# Main.net
KiCad netlist of a schematic drawn in Altium Designer
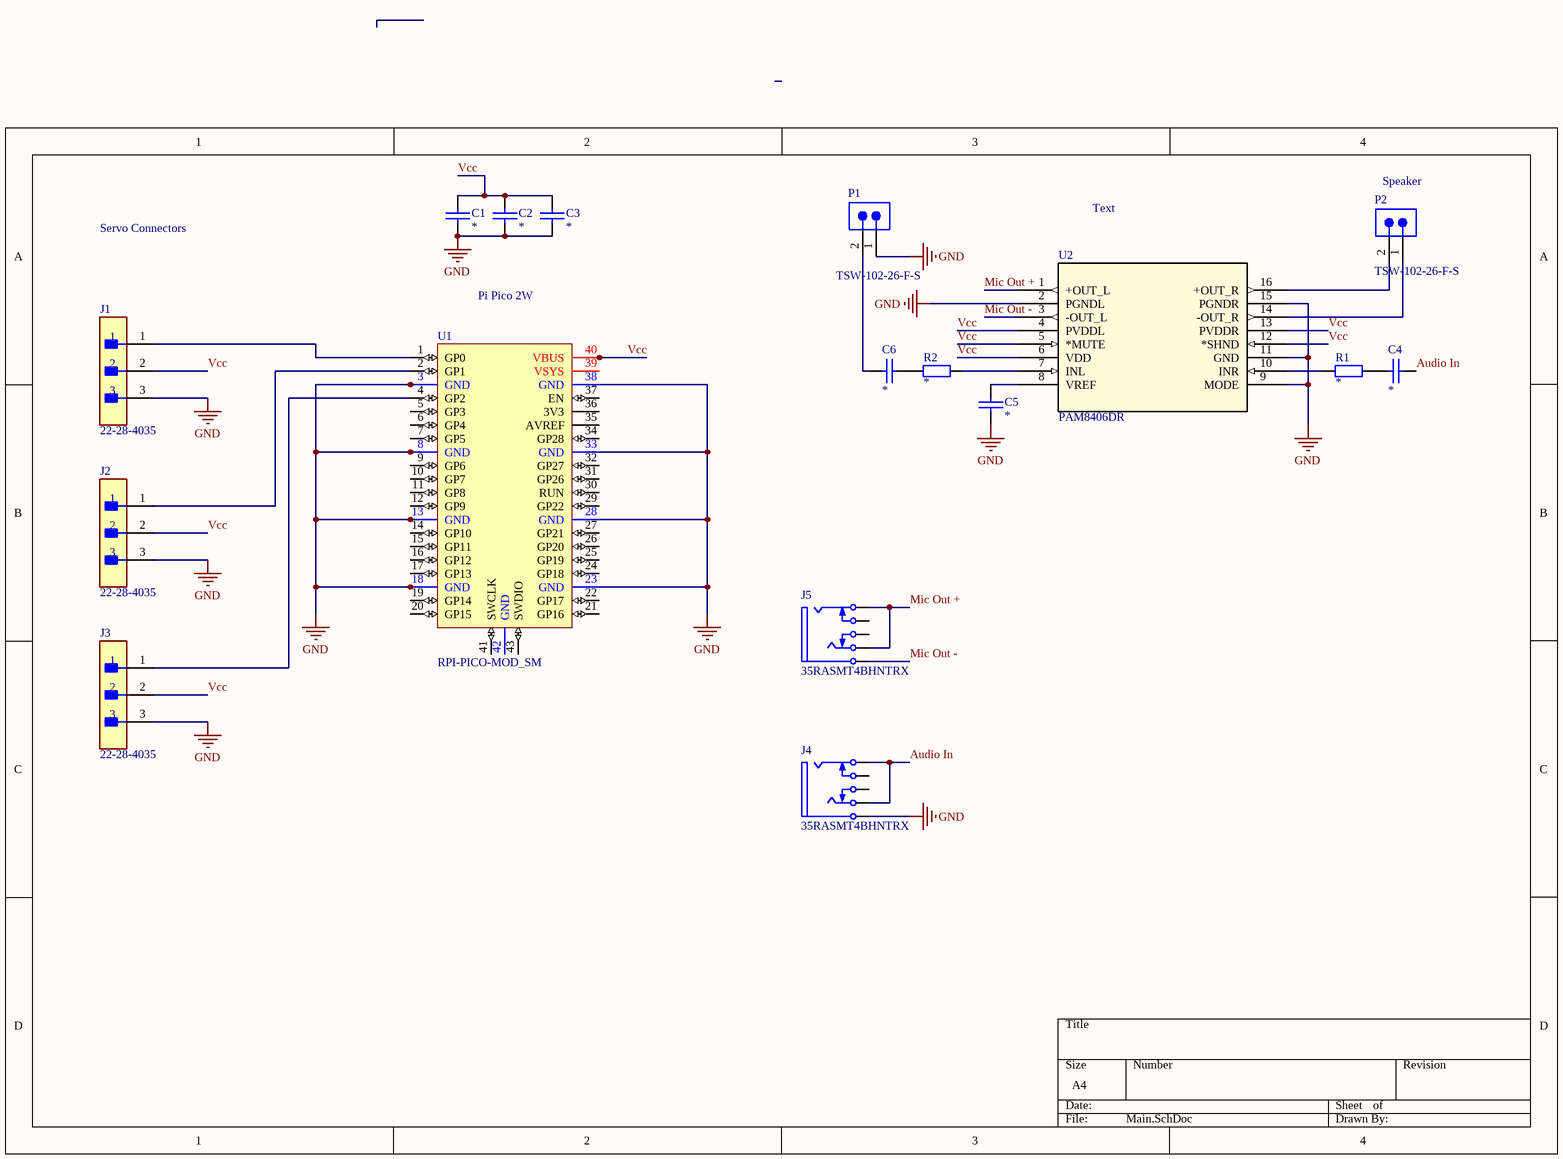
[diagram p0: Main.SchDoc]

(export (version "E")
  (design (tool "Eeschema 10.0.6"))
  (components
    (comp (ref "C1")
      (value "*")
      (footprint "0805 CAP")
      (description "SMT ceramic capacitor 0805 size")
      (libsource (lib "EE209_SchLib") (part "CerCap_SMT_0805"))
    )
    (comp (ref "C2")
      (value "*")
      (footprint "0805 CAP")
      (description "SMT ceramic capacitor 0805 size")
      (libsource (lib "EE209_SchLib") (part "CerCap_SMT_0805"))
    )
    (comp (ref "C3")
      (value "*")
      (footprint "0805 CAP")
      (description "SMT ceramic capacitor 0805 size")
      (libsource (lib "EE209_SchLib") (part "CerCap_SMT_0805"))
    )
    (comp (ref "C4")
      (value "*")
      (footprint "0805 CAP")
      (description "SMT ceramic capacitor 0805 size")
      (libsource (lib "EE209_SchLib") (part "CerCap_SMT_0805"))
    )
    (comp (ref "C5")
      (value "*")
      (footprint "0805 CAP")
      (description "SMT ceramic capacitor 0805 size")
      (libsource (lib "EE209_SchLib") (part "CerCap_SMT_0805"))
    )
    (comp (ref "C6")
      (value "*")
      (footprint "0805 CAP")
      (description "SMT ceramic capacitor 0805 size")
      (libsource (lib "EE209_SchLib") (part "CerCap_SMT_0805"))
    )
    (comp (ref "J1")
      (value "22-28-4035")
      (footprint "FP-22-28-4035-MFG")
      (libsource (lib "Altium Content Vault") (part "0d3f023dd272f625e17a2be33dea85f"))
    )
    (comp (ref "J2")
      (value "22-28-4035")
      (footprint "FP-22-28-4035-MFG")
      (libsource (lib "Altium Content Vault") (part "0d3f023dd272f625e17a2be33dea85f"))
    )
    (comp (ref "J3")
      (value "22-28-4035")
      (footprint "FP-22-28-4035-MFG")
      (libsource (lib "Altium Content Vault") (part "0d3f023dd272f625e17a2be33dea85f"))
    )
    (comp (ref "J4")
      (value "35RASMT4BHNTRX")
      (footprint "SWIT-35RASMT4BHNTRX_V")
      (description "Female 3.5 mm Phone Jack, 5 Position, Height 5 mm, RoHS, Tape and Reel")
      (libsource (lib "Altium Content Vault") (part "JACK-3CD5-RN"))
    )
    (comp (ref "J5")
      (value "35RASMT4BHNTRX")
      (footprint "SWIT-35RASMT4BHNTRX_V")
      (description "Female 3.5 mm Phone Jack, 5 Position, Height 5 mm, RoHS, Tape and Reel")
      (libsource (lib "Altium Content Vault") (part "JACK-3CD5-RN"))
    )
    (comp (ref "P1")
      (value "TSW-102-26-F-S")
      (footprint "SMTC-TSW-102-26-XX-S")
      (description "0.025\" SQ Post Header, Through-hole, Vertical, -55 to 125 degC, 2.54 mm Pitch, 2-Pin, Male, RoHS")
      (fields (field (name "MANUFACTURER") "Samtec"))
      (libsource (lib "Altium Content Vault") (part "SMTC-TSW-102-X-X-S-X"))
    )
    (comp (ref "P2")
      (value "TSW-102-26-F-S")
      (footprint "SMTC-TSW-102-26-XX-S")
      (description "0.025\" SQ Post Header, Through-hole, Vertical, -55 to 125 degC, 2.54 mm Pitch, 2-Pin, Male, RoHS")
      (fields (field (name "MANUFACTURER") "Samtec"))
      (libsource (lib "Altium Content Vault") (part "SMTC-TSW-102-X-X-S-X"))
    )
    (comp (ref "R1")
      (value "*")
      (footprint "0805 RES")
      (description "0805 resistor")
      (fields (field (name "PUBLISHER") "Altium Limited"))
      (libsource (lib "") (part "Res_SMT_0805_1"))
    )
    (comp (ref "R2")
      (value "*")
      (footprint "0805 RES")
      (description "0805 resistor")
      (fields (field (name "PUBLISHER") "Altium Limited"))
      (libsource (lib "EE209_SchLib") (part "Res_SMT_0805"))
    )
    (comp (ref "U1")
      (value "RPI-PICO-MOD_SM")
      (footprint "RPI-PICO-MOD")
      (description "RASPBERRY PI PICO RP2040 BOARD NO TEST PADS")
      (fields
        (field (name "MANUFACTURER") "Raspberry Pi Foundation")
        (field (name "MANUFACTURER PART NO") "SC0915")
      )
      (libsource (lib "RPi_Pico") (part "RPI-PICO-MOD_SM"))
    )
    (comp (ref "U2")
      (value "PAM8406DR")
      (footprint "SO-16_PAM8406_DIO")
      (description "Description")
      (fields (field (name "COPYRIGHT") "Copyright (C) 2025 Ultra Librarian. All rights reserved."))
      (libsource (lib "PAM8406DR") (part "PAM8406DR"))
    )
  )
  (nets
    (net (code "1") (name "/Audio In") (class "Default")
      (node (ref "C4") (pin "2") (pinfunction "2_2") (pintype "passive"))
      (node (ref "J4") (pin "2") (pinfunction "2_2") (pintype "passive"))
      (node (ref "J4") (pin "3") (pinfunction "3_3") (pintype "passive"))
    )
    (net (code "2") (name "/Mic Out +") (class "Default")
      (node (ref "J5") (pin "2") (pinfunction "2_2") (pintype "passive"))
      (node (ref "J5") (pin "3") (pinfunction "3_3") (pintype "passive"))
      (node (ref "U2") (pin "1") (pinfunction "+OUT_L_1") (pintype "output"))
    )
    (net (code "3") (name "/Mic Out -") (class "Default")
      (node (ref "J5") (pin "1") (pinfunction "1_1") (pintype "passive"))
      (node (ref "U2") (pin "3") (pinfunction "-OUT_L_3") (pintype "output"))
    )
    (net (code "4") (name "/Vcc") (class "Default")
      (node (ref "C1") (pin "1") (pinfunction "1_1") (pintype "passive"))
      (node (ref "C2") (pin "1") (pinfunction "1_1") (pintype "passive"))
      (node (ref "C3") (pin "1") (pinfunction "1_1") (pintype "passive"))
      (node (ref "J1") (pin "2") (pinfunction "2_2") (pintype "passive"))
      (node (ref "J2") (pin "2") (pinfunction "2_2") (pintype "passive"))
      (node (ref "J3") (pin "2") (pinfunction "2_2") (pintype "passive"))
      (node (ref "U1") (pin "40") (pinfunction "VBUS_40") (pintype "power_in"))
      (node (ref "U2") (pin "12") (pinfunction "*SHND_12") (pintype "input"))
      (node (ref "U2") (pin "13") (pinfunction "PVDDR_13") (pintype "power_in"))
      (node (ref "U2") (pin "4") (pinfunction "PVDDL_4") (pintype "power_in"))
      (node (ref "U2") (pin "5") (pinfunction "*MUTE_5") (pintype "input"))
      (node (ref "U2") (pin "6") (pinfunction "VDD_6") (pintype "power_in"))
    )
    (net (code "5") (name "GND") (class "Default")
      (node (ref "C1") (pin "2") (pinfunction "2_2") (pintype "passive"))
      (node (ref "C2") (pin "2") (pinfunction "2_2") (pintype "passive"))
      (node (ref "C3") (pin "2") (pinfunction "2_2") (pintype "passive"))
      (node (ref "C5") (pin "2") (pinfunction "2_2") (pintype "passive"))
      (node (ref "J1") (pin "3") (pinfunction "3_3") (pintype "passive"))
      (node (ref "J2") (pin "3") (pinfunction "3_3") (pintype "passive"))
      (node (ref "J3") (pin "3") (pinfunction "3_3") (pintype "passive"))
      (node (ref "J4") (pin "1") (pinfunction "1_1") (pintype "passive"))
      (node (ref "P1") (pin "1") (pinfunction "1_1") (pintype "passive"))
      (node (ref "U1") (pin "13") (pinfunction "GND_13") (pintype "power_in"))
      (node (ref "U1") (pin "18") (pinfunction "GND_18") (pintype "power_in"))
      (node (ref "U1") (pin "23") (pinfunction "GND_23") (pintype "power_in"))
      (node (ref "U1") (pin "28") (pinfunction "GND_28") (pintype "power_in"))
      (node (ref "U1") (pin "3") (pinfunction "GND_3") (pintype "power_in"))
      (node (ref "U1") (pin "33") (pinfunction "GND_33") (pintype "power_in"))
      (node (ref "U1") (pin "38") (pinfunction "GND_38") (pintype "power_in"))
      (node (ref "U1") (pin "8") (pinfunction "GND_8") (pintype "power_in"))
      (node (ref "U2") (pin "11") (pinfunction "GND_11") (pintype "power_in"))
      (node (ref "U2") (pin "15") (pinfunction "PGNDR_15") (pintype "power_in"))
      (node (ref "U2") (pin "2") (pinfunction "PGNDL_2") (pintype "power_in"))
      (node (ref "U2") (pin "9") (pinfunction "MODE_9") (pintype "passive"))
    )
    (net (code "6") (name "Net-(C4-Pad1)") (class "Default")
      (node (ref "C4") (pin "1") (pinfunction "1_1") (pintype "passive"))
      (node (ref "R1") (pin "2") (pinfunction "2_2") (pintype "passive"))
    )
    (net (code "7") (name "Net-(C6-Pad1)") (class "Default")
      (node (ref "C6") (pin "1") (pinfunction "1_1") (pintype "passive"))
      (node (ref "R2") (pin "2") (pinfunction "2_2") (pintype "passive"))
    )
    (net (code "8") (name "Net-(C6-Pad2)") (class "Default")
      (node (ref "C6") (pin "2") (pinfunction "2_2") (pintype "passive"))
      (node (ref "P1") (pin "2") (pinfunction "2_2") (pintype "passive"))
    )
    (net (code "9") (name "Net-(U1-GP0)") (class "Default")
      (node (ref "J1") (pin "1") (pinfunction "1_1") (pintype "passive"))
      (node (ref "U1") (pin "1") (pinfunction "GP0_1") (pintype "bidirectional"))
    )
    (net (code "10") (name "Net-(U1-GP1)") (class "Default")
      (node (ref "J2") (pin "1") (pinfunction "1_1") (pintype "passive"))
      (node (ref "U1") (pin "2") (pinfunction "GP1_2") (pintype "bidirectional"))
    )
    (net (code "11") (name "Net-(U1-GP2)") (class "Default")
      (node (ref "J3") (pin "1") (pinfunction "1_1") (pintype "passive"))
      (node (ref "U1") (pin "4") (pinfunction "GP2_4") (pintype "bidirectional"))
    )
    (net (code "12") (name "Net-(U2-+OUT_R)") (class "Default")
      (node (ref "P2") (pin "2") (pinfunction "2_2") (pintype "passive"))
      (node (ref "U2") (pin "16") (pinfunction "+OUT_R_16") (pintype "output"))
    )
    (net (code "13") (name "Net-(U2--OUT_R)") (class "Default")
      (node (ref "P2") (pin "1") (pinfunction "1_1") (pintype "passive"))
      (node (ref "U2") (pin "14") (pinfunction "-OUT_R_14") (pintype "output"))
    )
    (net (code "14") (name "Net-(U2-INL)") (class "Default")
      (node (ref "R2") (pin "1") (pinfunction "1_1") (pintype "passive"))
      (node (ref "U2") (pin "7") (pinfunction "INL_7") (pintype "input"))
    )
    (net (code "15") (name "Net-(U2-INR)") (class "Default")
      (node (ref "R1") (pin "1") (pinfunction "1_1") (pintype "passive"))
      (node (ref "U2") (pin "10") (pinfunction "INR_10") (pintype "input"))
    )
    (net (code "16") (name "Net-(U2-VREF)") (class "Default")
      (node (ref "C5") (pin "1") (pinfunction "1_1") (pintype "passive"))
      (node (ref "U2") (pin "8") (pinfunction "VREF_8") (pintype "power_in"))
    )
    (net (code "17") (name "unconnected-(J4-Pad4)") (class "Default")
      (node (ref "J4") (pin "4") (pinfunction "4_4") (pintype "passive"))
    )
    (net (code "18") (name "unconnected-(J4-Pad5)") (class "Default")
      (node (ref "J4") (pin "5") (pinfunction "5_5") (pintype "passive"))
    )
    (net (code "19") (name "unconnected-(J5-Pad4)") (class "Default")
      (node (ref "J5") (pin "4") (pinfunction "4_4") (pintype "passive"))
    )
    (net (code "20") (name "unconnected-(J5-Pad5)") (class "Default")
      (node (ref "J5") (pin "5") (pinfunction "5_5") (pintype "passive"))
    )
    (net (code "21") (name "unconnected-(U1-3V3-Pad36)") (class "Default")
      (node (ref "U1") (pin "36") (pinfunction "3V3_36") (pintype "power_in"))
    )
    (net (code "22") (name "unconnected-(U1-AVREF-Pad35)") (class "Default")
      (node (ref "U1") (pin "35") (pinfunction "AVREF_35") (pintype "power_in"))
    )
    (net (code "23") (name "unconnected-(U1-EN-Pad37)") (class "Default")
      (node (ref "U1") (pin "37") (pinfunction "EN_37") (pintype "bidirectional"))
    )
    (net (code "24") (name "unconnected-(U1-GND-Pad42)") (class "Default")
      (node (ref "U1") (pin "42") (pinfunction "GND_42") (pintype "power_in"))
    )
    (net (code "25") (name "unconnected-(U1-GP3-Pad5)") (class "Default")
      (node (ref "U1") (pin "5") (pinfunction "GP3_5") (pintype "bidirectional"))
    )
    (net (code "26") (name "unconnected-(U1-GP4-Pad6)") (class "Default")
      (node (ref "U1") (pin "6") (pinfunction "GP4_6") (pintype "bidirectional"))
    )
    (net (code "27") (name "unconnected-(U1-GP5-Pad7)") (class "Default")
      (node (ref "U1") (pin "7") (pinfunction "GP5_7") (pintype "bidirectional"))
    )
    (net (code "28") (name "unconnected-(U1-GP6-Pad9)") (class "Default")
      (node (ref "U1") (pin "9") (pinfunction "GP6_9") (pintype "bidirectional"))
    )
    (net (code "29") (name "unconnected-(U1-GP7-Pad10)") (class "Default")
      (node (ref "U1") (pin "10") (pinfunction "GP7_10") (pintype "bidirectional"))
    )
    (net (code "30") (name "unconnected-(U1-GP8-Pad11)") (class "Default")
      (node (ref "U1") (pin "11") (pinfunction "GP8_11") (pintype "bidirectional"))
    )
    (net (code "31") (name "unconnected-(U1-GP9-Pad12)") (class "Default")
      (node (ref "U1") (pin "12") (pinfunction "GP9_12") (pintype "bidirectional"))
    )
    (net (code "32") (name "unconnected-(U1-GP10-Pad14)") (class "Default")
      (node (ref "U1") (pin "14") (pinfunction "GP10_14") (pintype "bidirectional"))
    )
    (net (code "33") (name "unconnected-(U1-GP11-Pad15)") (class "Default")
      (node (ref "U1") (pin "15") (pinfunction "GP11_15") (pintype "bidirectional"))
    )
    (net (code "34") (name "unconnected-(U1-GP12-Pad16)") (class "Default")
      (node (ref "U1") (pin "16") (pinfunction "GP12_16") (pintype "bidirectional"))
    )
    (net (code "35") (name "unconnected-(U1-GP13-Pad17)") (class "Default")
      (node (ref "U1") (pin "17") (pinfunction "GP13_17") (pintype "bidirectional"))
    )
    (net (code "36") (name "unconnected-(U1-GP14-Pad19)") (class "Default")
      (node (ref "U1") (pin "19") (pinfunction "GP14_19") (pintype "bidirectional"))
    )
    (net (code "37") (name "unconnected-(U1-GP15-Pad20)") (class "Default")
      (node (ref "U1") (pin "20") (pinfunction "GP15_20") (pintype "bidirectional"))
    )
    (net (code "38") (name "unconnected-(U1-GP16-Pad21)") (class "Default")
      (node (ref "U1") (pin "21") (pinfunction "GP16_21") (pintype "bidirectional"))
    )
    (net (code "39") (name "unconnected-(U1-GP17-Pad22)") (class "Default")
      (node (ref "U1") (pin "22") (pinfunction "GP17_22") (pintype "bidirectional"))
    )
    (net (code "40") (name "unconnected-(U1-GP18-Pad24)") (class "Default")
      (node (ref "U1") (pin "24") (pinfunction "GP18_24") (pintype "bidirectional"))
    )
    (net (code "41") (name "unconnected-(U1-GP19-Pad25)") (class "Default")
      (node (ref "U1") (pin "25") (pinfunction "GP19_25") (pintype "bidirectional"))
    )
    (net (code "42") (name "unconnected-(U1-GP20-Pad26)") (class "Default")
      (node (ref "U1") (pin "26") (pinfunction "GP20_26") (pintype "bidirectional"))
    )
    (net (code "43") (name "unconnected-(U1-GP21-Pad27)") (class "Default")
      (node (ref "U1") (pin "27") (pinfunction "GP21_27") (pintype "bidirectional"))
    )
    (net (code "44") (name "unconnected-(U1-GP22-Pad29)") (class "Default")
      (node (ref "U1") (pin "29") (pinfunction "GP22_29") (pintype "bidirectional"))
    )
    (net (code "45") (name "unconnected-(U1-GP26-Pad31)") (class "Default")
      (node (ref "U1") (pin "31") (pinfunction "GP26_31") (pintype "bidirectional"))
    )
    (net (code "46") (name "unconnected-(U1-GP27-Pad32)") (class "Default")
      (node (ref "U1") (pin "32") (pinfunction "GP27_32") (pintype "bidirectional"))
    )
    (net (code "47") (name "unconnected-(U1-GP28-Pad34)") (class "Default")
      (node (ref "U1") (pin "34") (pinfunction "GP28_34") (pintype "bidirectional"))
    )
    (net (code "48") (name "unconnected-(U1-RUN-Pad30)") (class "Default")
      (node (ref "U1") (pin "30") (pinfunction "RUN_30") (pintype "bidirectional"))
    )
    (net (code "49") (name "unconnected-(U1-SWCLK-Pad41)") (class "Default")
      (node (ref "U1") (pin "41") (pinfunction "SWCLK_41") (pintype "bidirectional"))
    )
    (net (code "50") (name "unconnected-(U1-SWDIO-Pad43)") (class "Default")
      (node (ref "U1") (pin "43") (pinfunction "SWDIO_43") (pintype "bidirectional"))
    )
    (net (code "51") (name "unconnected-(U1-VSYS-Pad39)") (class "Default")
      (node (ref "U1") (pin "39") (pinfunction "VSYS_39") (pintype "power_in"))
    )
  )
)
